# regulador_3v3.net
KiCad netlist of a schematic drawn in EAGLE
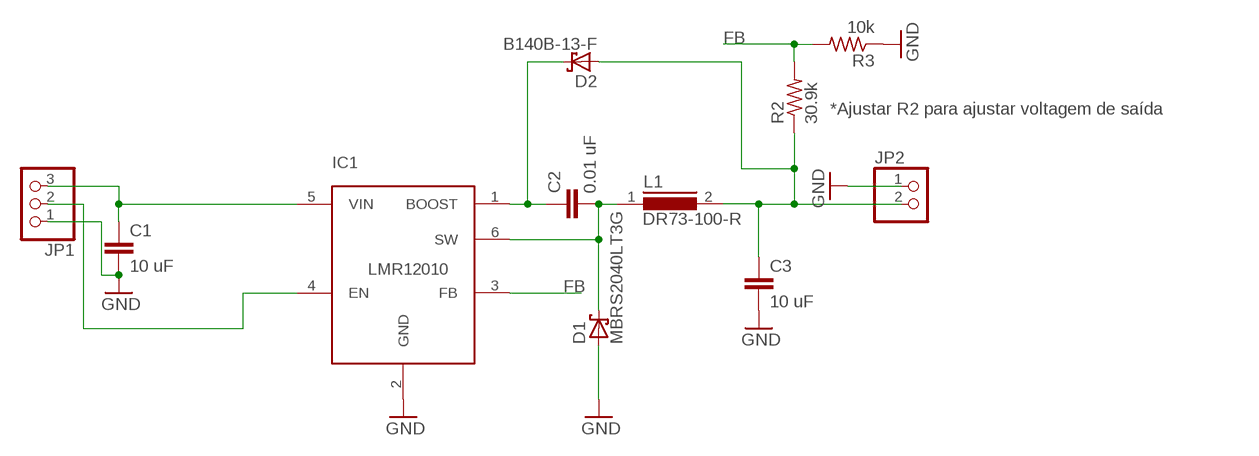
[diagram p0: schematic, sheet 1]

(export (version "E")
  (design (tool "Eeschema 10.0.6"))
  (components
    (comp (ref "C1")
      (value "10 uF")
      (footprint "eagle-import:C1210")
      (libsource (lib "eagle-import") (part "C-EUC1210"))
    )
    (comp (ref "C2")
      (value "0.01 uF")
      (footprint "eagle-import:C0805")
      (libsource (lib "eagle-import") (part "C-EUC0805"))
    )
    (comp (ref "C3")
      (value "10 uF")
      (footprint "eagle-import:C1210")
      (libsource (lib "eagle-import") (part "C-EUC1210"))
    )
    (comp (ref "D1")
      (value "MBRS2040LT3G")
      (footprint "eagle-import:SMB")
      (libsource (lib "eagle-import") (part "MBRS130LT3"))
    )
    (comp (ref "D2")
      (value "B140B-13-F")
      (footprint "eagle-import:SMB")
      (libsource (lib "eagle-import") (part "MBRS130LT3"))
    )
    (comp (ref "IC1")
      (value "LMR12010")
      (footprint "eagle-import:SOT23-6L")
      (libsource (lib "eagle-import") (part "LMR12010"))
    )
    (comp (ref "JP1")
      (value "PINHD-1X3")
      (footprint "eagle-import:1X03")
      (libsource (lib "eagle-import") (part "PINHD-1X3"))
    )
    (comp (ref "JP2")
      (value "PINHD-1X2")
      (footprint "eagle-import:1X02")
      (libsource (lib "eagle-import") (part "PINHD-1X2"))
    )
    (comp (ref "L1")
      (value "DR73-100-R")
      (footprint "eagle-import:DR73")
      (libsource (lib "eagle-import") (part "DR73"))
    )
    (comp (ref "R2")
      (value "30.9k")
      (footprint "eagle-import:R0805")
      (libsource (lib "eagle-import") (part "R-US_R0805"))
    )
    (comp (ref "R3")
      (value "10k")
      (footprint "eagle-import:R0805")
      (libsource (lib "eagle-import") (part "R-US_R0805"))
    )
  )
  (nets
    (net (code "1") (name "/FB") (class "Default")
      (node (ref "IC1") (pin "3") (pinfunction "FB_3") (pintype "bidirectional"))
      (node (ref "R2") (pin "2") (pinfunction "2_2") (pintype "passive"))
      (node (ref "R3") (pin "2") (pinfunction "2_2") (pintype "passive"))
    )
    (net (code "2") (name "GND") (class "Default")
      (node (ref "C1") (pin "2") (pinfunction "2_2") (pintype "passive"))
      (node (ref "C3") (pin "2") (pinfunction "2_2") (pintype "passive"))
      (node (ref "D1") (pin "A") (pinfunction "A_A") (pintype "passive"))
      (node (ref "IC1") (pin "2") (pinfunction "GND_2") (pintype "bidirectional"))
      (node (ref "JP1") (pin "1") (pinfunction "1_1") (pintype "passive"))
      (node (ref "JP2") (pin "1") (pinfunction "1_1") (pintype "passive"))
      (node (ref "R3") (pin "1") (pinfunction "1_1") (pintype "passive"))
    )
    (net (code "3") (name "Net-(C3-Pad1)") (class "Default")
      (node (ref "C3") (pin "1") (pinfunction "1_1") (pintype "passive"))
      (node (ref "D2") (pin "A") (pinfunction "A_A") (pintype "passive"))
      (node (ref "JP2") (pin "2") (pinfunction "2_2") (pintype "passive"))
      (node (ref "L1") (pin "2") (pinfunction "2_2") (pintype "passive"))
      (node (ref "R2") (pin "1") (pinfunction "1_1") (pintype "passive"))
    )
    (net (code "4") (name "Net-(IC1-BOOST)") (class "Default")
      (node (ref "C2") (pin "1") (pinfunction "1_1") (pintype "passive"))
      (node (ref "D2") (pin "C") (pinfunction "C_C") (pintype "passive"))
      (node (ref "IC1") (pin "1") (pinfunction "BOOST_1") (pintype "bidirectional"))
    )
    (net (code "5") (name "Net-(IC1-EN)") (class "Default")
      (node (ref "IC1") (pin "4") (pinfunction "EN_4") (pintype "bidirectional"))
      (node (ref "JP1") (pin "2") (pinfunction "2_2") (pintype "passive"))
    )
    (net (code "6") (name "Net-(IC1-SW)") (class "Default")
      (node (ref "C2") (pin "2") (pinfunction "2_2") (pintype "passive"))
      (node (ref "D1") (pin "C") (pinfunction "C_C") (pintype "passive"))
      (node (ref "IC1") (pin "6") (pinfunction "SW_6") (pintype "bidirectional"))
      (node (ref "L1") (pin "1") (pinfunction "1_1") (pintype "passive"))
    )
    (net (code "7") (name "Net-(IC1-VIN)") (class "Default")
      (node (ref "C1") (pin "1") (pinfunction "1_1") (pintype "passive"))
      (node (ref "IC1") (pin "5") (pinfunction "VIN_5") (pintype "bidirectional"))
      (node (ref "JP1") (pin "3") (pinfunction "3_3") (pintype "passive"))
    )
  )
)
